# LEDBOARD_v2.net
KiCad netlist of a schematic drawn in EAGLE
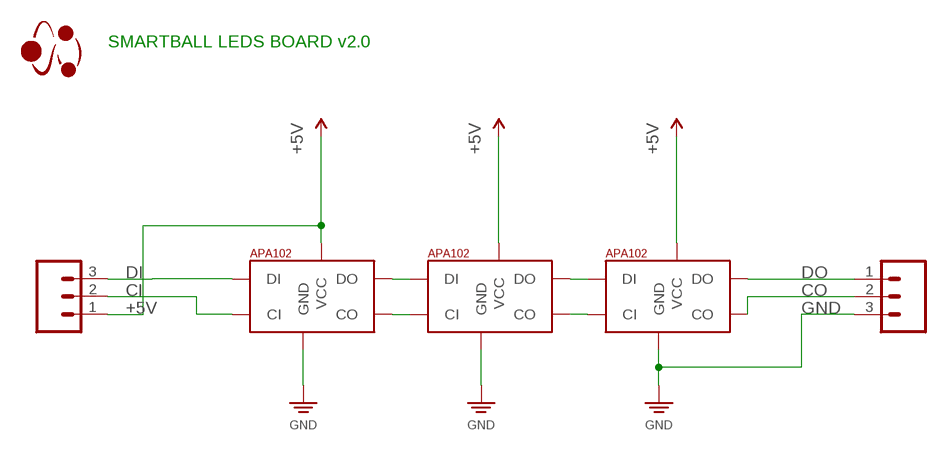
[diagram p0: schematic, sheet 1]

(export (version "E")
  (design (tool "Eeschema 10.0.6"))
  (components
    (comp (ref "L1")
      (value "APA102")
      (footprint "eagle-import:APA102_5050_SB")
      (libsource (lib "eagle-import") (part "APA102"))
    )
    (comp (ref "L2")
      (value "APA102")
      (footprint "eagle-import:APA102_5050_SB")
      (libsource (lib "eagle-import") (part "APA102"))
    )
    (comp (ref "L3")
      (value "APA102")
      (footprint "eagle-import:APA102_5050_SB")
      (libsource (lib "eagle-import") (part "APA102"))
    )
    (comp (ref "U$4")
      (value "LOGO_SMARTBALL")
      (footprint "eagle-import:SMARTBALL_LOGO")
      (libsource (lib "eagle-import") (part "LOGO_SMARTBALL"))
    )
    (comp (ref "U$5")
      (value "CONN_03_SMD_MALECONN03_SMD_MALE")
      (footprint "eagle-import:CONN03_SMD_MALE")
      (libsource (lib "eagle-import") (part "CONN_03_SMD_MALECONN03_SMD_MALE"))
    )
    (comp (ref "U$6")
      (value "CONN_03_SMD_MALECONN03_SMD_MALE")
      (footprint "eagle-import:CONN03_SMD_MALE")
      (libsource (lib "eagle-import") (part "CONN_03_SMD_MALECONN03_SMD_MALE"))
    )
  )
  (nets
    (net (code "1") (name "+5V") (class "Default")
      (node (ref "L1") (pin "4") (pinfunction "VCC_4") (pintype "bidirectional"))
      (node (ref "L2") (pin "4") (pinfunction "VCC_4") (pintype "bidirectional"))
      (node (ref "L3") (pin "4") (pinfunction "VCC_4") (pintype "bidirectional"))
      (node (ref "U$5") (pin "1") (pinfunction "1_1") (pintype "passive"))
    )
    (net (code "2") (name "/CI") (class "Default")
      (node (ref "L1") (pin "2") (pinfunction "CI_2") (pintype "bidirectional"))
      (node (ref "L1") (pin "CI2") (pinfunction "CI_CI2") (pintype "bidirectional"))
      (node (ref "U$5") (pin "2") (pinfunction "2_2") (pintype "passive"))
    )
    (net (code "3") (name "/CO") (class "Default")
      (node (ref "L3") (pin "5") (pinfunction "CO_5") (pintype "bidirectional"))
      (node (ref "U$6") (pin "2") (pinfunction "2_2") (pintype "passive"))
    )
    (net (code "4") (name "/DI") (class "Default")
      (node (ref "L1") (pin "1") (pinfunction "DI_1") (pintype "bidirectional"))
      (node (ref "L1") (pin "DI2") (pinfunction "DI_DI2") (pintype "bidirectional"))
      (node (ref "U$5") (pin "3") (pinfunction "3_3") (pintype "passive"))
    )
    (net (code "5") (name "/DO") (class "Default")
      (node (ref "L3") (pin "6") (pinfunction "DO_6") (pintype "bidirectional"))
      (node (ref "U$6") (pin "1") (pinfunction "1_1") (pintype "passive"))
    )
    (net (code "6") (name "GND") (class "Default")
      (node (ref "L1") (pin "3") (pinfunction "GND_3") (pintype "bidirectional"))
      (node (ref "L1") (pin "GND2") (pinfunction "GND_GND2") (pintype "bidirectional"))
      (node (ref "L2") (pin "3") (pinfunction "GND_3") (pintype "bidirectional"))
      (node (ref "L2") (pin "GND2") (pinfunction "GND_GND2") (pintype "bidirectional"))
      (node (ref "L3") (pin "3") (pinfunction "GND_3") (pintype "bidirectional"))
      (node (ref "L3") (pin "GND2") (pinfunction "GND_GND2") (pintype "bidirectional"))
      (node (ref "U$6") (pin "3") (pinfunction "3_3") (pintype "passive"))
    )
    (net (code "7") (name "Net-(L1-CO)") (class "Default")
      (node (ref "L1") (pin "5") (pinfunction "CO_5") (pintype "bidirectional"))
      (node (ref "L2") (pin "2") (pinfunction "CI_2") (pintype "bidirectional"))
      (node (ref "L2") (pin "CI2") (pinfunction "CI_CI2") (pintype "bidirectional"))
    )
    (net (code "8") (name "Net-(L1-DO)") (class "Default")
      (node (ref "L1") (pin "6") (pinfunction "DO_6") (pintype "bidirectional"))
      (node (ref "L2") (pin "1") (pinfunction "DI_1") (pintype "bidirectional"))
      (node (ref "L2") (pin "DI2") (pinfunction "DI_DI2") (pintype "bidirectional"))
    )
    (net (code "9") (name "Net-(L2-CO)") (class "Default")
      (node (ref "L2") (pin "5") (pinfunction "CO_5") (pintype "bidirectional"))
      (node (ref "L3") (pin "2") (pinfunction "CI_2") (pintype "bidirectional"))
      (node (ref "L3") (pin "CI2") (pinfunction "CI_CI2") (pintype "bidirectional"))
    )
    (net (code "10") (name "Net-(L2-DO)") (class "Default")
      (node (ref "L2") (pin "6") (pinfunction "DO_6") (pintype "bidirectional"))
      (node (ref "L3") (pin "1") (pinfunction "DI_1") (pintype "bidirectional"))
      (node (ref "L3") (pin "DI2") (pinfunction "DI_DI2") (pintype "bidirectional"))
    )
  )
)
